# v002.net
KiCad netlist of a schematic drawn in EAGLE
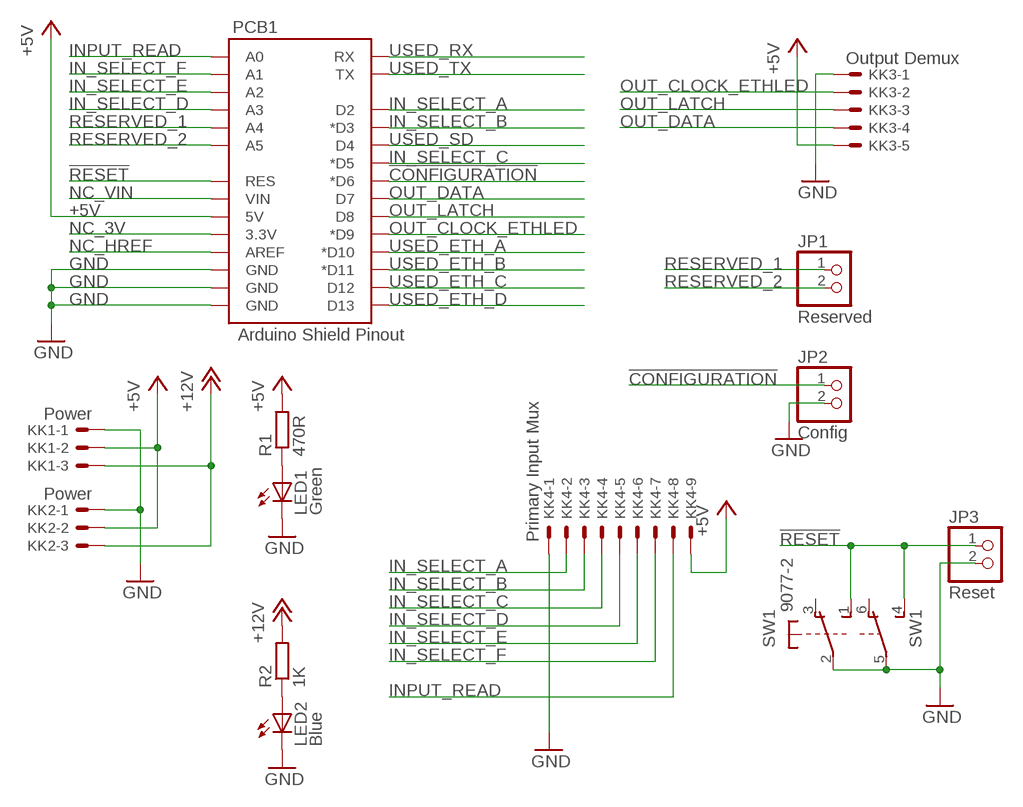
[diagram p0: schematic, sheet 1]

(export (version "E")
  (design (tool "Eeschema 10.0.6"))
  (components
    (comp (ref "JP1")
      (value "Reserved")
      (footprint "eagle-import:1X02")
      (libsource (lib "eagle-import") (part "PINHD-1X2"))
    )
    (comp (ref "JP2")
      (value "Config")
      (footprint "eagle-import:1X02")
      (libsource (lib "eagle-import") (part "PINHD-1X2"))
    )
    (comp (ref "JP3")
      (value "Reset")
      (footprint "eagle-import:1X02")
      (libsource (lib "eagle-import") (part "PINHD-1X2"))
    )
    (comp (ref "KK1")
      (value "Power")
      (footprint "eagle-import:6410-03")
      (libsource (lib "eagle-import") (part "22-?-0327-2031"))
    )
    (comp (ref "KK2")
      (value "Power")
      (footprint "eagle-import:6410-03")
      (libsource (lib "eagle-import") (part "22-?-0327-2031"))
    )
    (comp (ref "KK3")
      (value "Output Demux")
      (footprint "eagle-import:6410-05")
      (libsource (lib "eagle-import") (part "22-?-0527-2051"))
    )
    (comp (ref "KK4")
      (value "Primary Input Mux")
      (footprint "eagle-import:6410-09")
      (libsource (lib "eagle-import") (part "22-?-0927-2091"))
    )
    (comp (ref "LED1")
      (value "Green")
      (footprint "eagle-import:LED3MM")
      (libsource (lib "eagle-import") (part "LED3MM"))
    )
    (comp (ref "LED2")
      (value "Blue")
      (footprint "eagle-import:LED3MM")
      (libsource (lib "eagle-import") (part "LED3MM"))
    )
    (comp (ref "PCB1")
      (value "Arduino Shield Pinout")
      (footprint "eagle-import:DUEMILANOVE_SHIELD_LONGPADS")
      (libsource (lib "eagle-import") (part "ARDUINO_SHIELDLONGPADS"))
    )
    (comp (ref "R1")
      (value "470R")
      (footprint "eagle-import:0204_7")
      (libsource (lib "eagle-import") (part "R-EU_0204/7"))
    )
    (comp (ref "R2")
      (value "1K")
      (footprint "eagle-import:0204_7")
      (libsource (lib "eagle-import") (part "R-EU_0204/7"))
    )
    (comp (ref "SW1")
      (value "9077-2")
      (footprint "eagle-import:9077-2")
      (libsource (lib "eagle-import") (part "9077-2"))
    )
  )
  (nets
    (net (code "1") (name "+5V") (class "Default")
      (node (ref "KK1") (pin "2") (pinfunction "S_2") (pintype "passive"))
      (node (ref "KK2") (pin "2") (pinfunction "S_2") (pintype "passive"))
      (node (ref "KK3") (pin "5") (pinfunction "S_5") (pintype "passive"))
      (node (ref "KK4") (pin "9") (pinfunction "S_9") (pintype "passive"))
      (node (ref "PCB1") (pin "5V") (pinfunction "5V_5V") (pintype "bidirectional"))
      (node (ref "R1") (pin "2") (pinfunction "2_2") (pintype "passive"))
    )
    (net (code "2") (name "+12V") (class "Default")
      (node (ref "KK1") (pin "3") (pinfunction "S_3") (pintype "passive"))
      (node (ref "KK2") (pin "3") (pinfunction "S_3") (pintype "passive"))
      (node (ref "R2") (pin "2") (pinfunction "2_2") (pintype "passive"))
    )
    (net (code "3") (name "/INPUT_READ") (class "Default")
      (node (ref "KK4") (pin "8") (pinfunction "S_8") (pintype "passive"))
      (node (ref "PCB1") (pin "A0") (pinfunction "A0_A0") (pintype "bidirectional"))
    )
    (net (code "4") (name "/IN_SELECT_A") (class "Default")
      (node (ref "KK4") (pin "2") (pinfunction "S_2") (pintype "passive"))
      (node (ref "PCB1") (pin "D2") (pinfunction "D2_D2") (pintype "bidirectional"))
    )
    (net (code "5") (name "/IN_SELECT_B") (class "Default")
      (node (ref "KK4") (pin "3") (pinfunction "S_3") (pintype "passive"))
      (node (ref "PCB1") (pin "D3") (pinfunction "*D3_D3") (pintype "bidirectional"))
    )
    (net (code "6") (name "/IN_SELECT_C") (class "Default")
      (node (ref "KK4") (pin "4") (pinfunction "S_4") (pintype "passive"))
      (node (ref "PCB1") (pin "D5") (pinfunction "*D5_D5") (pintype "bidirectional"))
    )
    (net (code "7") (name "/IN_SELECT_D") (class "Default")
      (node (ref "KK4") (pin "5") (pinfunction "S_5") (pintype "passive"))
      (node (ref "PCB1") (pin "A3") (pinfunction "A3_A3") (pintype "bidirectional"))
    )
    (net (code "8") (name "/IN_SELECT_E") (class "Default")
      (node (ref "KK4") (pin "6") (pinfunction "S_6") (pintype "passive"))
      (node (ref "PCB1") (pin "A2") (pinfunction "A2_A2") (pintype "bidirectional"))
    )
    (net (code "9") (name "/IN_SELECT_F") (class "Default")
      (node (ref "KK4") (pin "7") (pinfunction "S_7") (pintype "passive"))
      (node (ref "PCB1") (pin "A1") (pinfunction "A1_A1") (pintype "bidirectional"))
    )
    (net (code "10") (name "/NC_3V") (class "Default")
      (node (ref "PCB1") (pin "3.3V") (pinfunction "3.3V_3.3V") (pintype "bidirectional"))
    )
    (net (code "11") (name "/NC_HREF") (class "Default")
      (node (ref "PCB1") (pin "AREF") (pinfunction "AREF_AREF") (pintype "bidirectional"))
    )
    (net (code "12") (name "/NC_VIN") (class "Default")
      (node (ref "PCB1") (pin "VIN") (pinfunction "VIN_VIN") (pintype "bidirectional"))
    )
    (net (code "13") (name "/OUT_CLOCK_ETHLED") (class "Default")
      (node (ref "KK3") (pin "2") (pinfunction "S_2") (pintype "passive"))
      (node (ref "PCB1") (pin "D9") (pinfunction "*D9_D9") (pintype "bidirectional"))
    )
    (net (code "14") (name "/OUT_DATA") (class "Default")
      (node (ref "KK3") (pin "4") (pinfunction "S_4") (pintype "passive"))
      (node (ref "PCB1") (pin "D7") (pinfunction "D7_D7") (pintype "bidirectional"))
    )
    (net (code "15") (name "/OUT_LATCH") (class "Default")
      (node (ref "KK3") (pin "3") (pinfunction "S_3") (pintype "passive"))
      (node (ref "PCB1") (pin "D8") (pinfunction "D8_D8") (pintype "bidirectional"))
    )
    (net (code "16") (name "/RESERVED_1") (class "Default")
      (node (ref "JP1") (pin "1") (pinfunction "1_1") (pintype "passive"))
      (node (ref "PCB1") (pin "A4") (pinfunction "A4_A4") (pintype "bidirectional"))
    )
    (net (code "17") (name "/RESERVED_2") (class "Default")
      (node (ref "JP1") (pin "2") (pinfunction "2_2") (pintype "passive"))
      (node (ref "PCB1") (pin "A5") (pinfunction "A5_A5") (pintype "bidirectional"))
    )
    (net (code "18") (name "/USED_ETH_A") (class "Default")
      (node (ref "PCB1") (pin "D10") (pinfunction "*D10_D10") (pintype "bidirectional"))
    )
    (net (code "19") (name "/USED_ETH_B") (class "Default")
      (node (ref "PCB1") (pin "D11") (pinfunction "*D11_D11") (pintype "bidirectional"))
    )
    (net (code "20") (name "/USED_ETH_C") (class "Default")
      (node (ref "PCB1") (pin "D12") (pinfunction "D12_D12") (pintype "bidirectional"))
    )
    (net (code "21") (name "/USED_ETH_D") (class "Default")
      (node (ref "PCB1") (pin "D13") (pinfunction "D13_D13") (pintype "bidirectional"))
    )
    (net (code "22") (name "/USED_RX") (class "Default")
      (node (ref "PCB1") (pin "RX") (pinfunction "RX_RX") (pintype "bidirectional"))
    )
    (net (code "23") (name "/USED_SD") (class "Default")
      (node (ref "PCB1") (pin "D4") (pinfunction "D4_D4") (pintype "bidirectional"))
    )
    (net (code "24") (name "/USED_TX") (class "Default")
      (node (ref "PCB1") (pin "TX") (pinfunction "TX_TX") (pintype "bidirectional"))
    )
    (net (code "25") (name "/~{CONFIGURATION}") (class "Default")
      (node (ref "JP2") (pin "1") (pinfunction "1_1") (pintype "passive"))
      (node (ref "PCB1") (pin "D6") (pinfunction "*D6_D6") (pintype "bidirectional"))
    )
    (net (code "26") (name "/~{RESET}") (class "Default")
      (node (ref "JP3") (pin "1") (pinfunction "1_1") (pintype "passive"))
      (node (ref "PCB1") (pin "RES") (pinfunction "RES_RES") (pintype "bidirectional"))
      (node (ref "SW1") (pin "1") (pinfunction "S_1") (pintype "passive"))
      (node (ref "SW1") (pin "4") (pinfunction "S_4") (pintype "passive"))
    )
    (net (code "27") (name "GND") (class "Default")
      (node (ref "JP2") (pin "2") (pinfunction "2_2") (pintype "passive"))
      (node (ref "JP3") (pin "2") (pinfunction "2_2") (pintype "passive"))
      (node (ref "KK1") (pin "1") (pinfunction "S_1") (pintype "passive"))
      (node (ref "KK2") (pin "1") (pinfunction "S_1") (pintype "passive"))
      (node (ref "KK3") (pin "1") (pinfunction "S_1") (pintype "passive"))
      (node (ref "KK4") (pin "1") (pinfunction "S_1") (pintype "passive"))
      (node (ref "LED1") (pin "K") (pinfunction "C_K") (pintype "passive"))
      (node (ref "LED2") (pin "K") (pinfunction "C_K") (pintype "passive"))
      (node (ref "PCB1") (pin "GND@0") (pinfunction "GND_GND@0") (pintype "bidirectional"))
      (node (ref "PCB1") (pin "GND@1") (pinfunction "GND_GND@1") (pintype "bidirectional"))
      (node (ref "PCB1") (pin "GND@2") (pinfunction "GND_GND@2") (pintype "bidirectional"))
      (node (ref "SW1") (pin "2") (pinfunction "P_2") (pintype "passive"))
      (node (ref "SW1") (pin "5") (pinfunction "P_5") (pintype "passive"))
    )
    (net (code "28") (name "Net-(LED1-PadA)") (class "Default")
      (node (ref "LED1") (pin "A") (pinfunction "A_A") (pintype "passive"))
      (node (ref "R1") (pin "1") (pinfunction "1_1") (pintype "passive"))
    )
    (net (code "29") (name "Net-(LED2-PadA)") (class "Default")
      (node (ref "LED2") (pin "A") (pinfunction "A_A") (pintype "passive"))
      (node (ref "R2") (pin "1") (pinfunction "1_1") (pintype "passive"))
    )
    (net (code "30") (name "unconnected-(SW1A-O-Pad3)") (class "Default")
      (node (ref "SW1") (pin "3") (pinfunction "O_3") (pintype "passive"))
    )
    (net (code "31") (name "unconnected-(SW1B-O-Pad6)") (class "Default")
      (node (ref "SW1") (pin "6") (pinfunction "O_6") (pintype "passive"))
    )
  )
)
